# attinier84-motherboard-mk-2_1.net
KiCad netlist of a schematic drawn in EAGLE
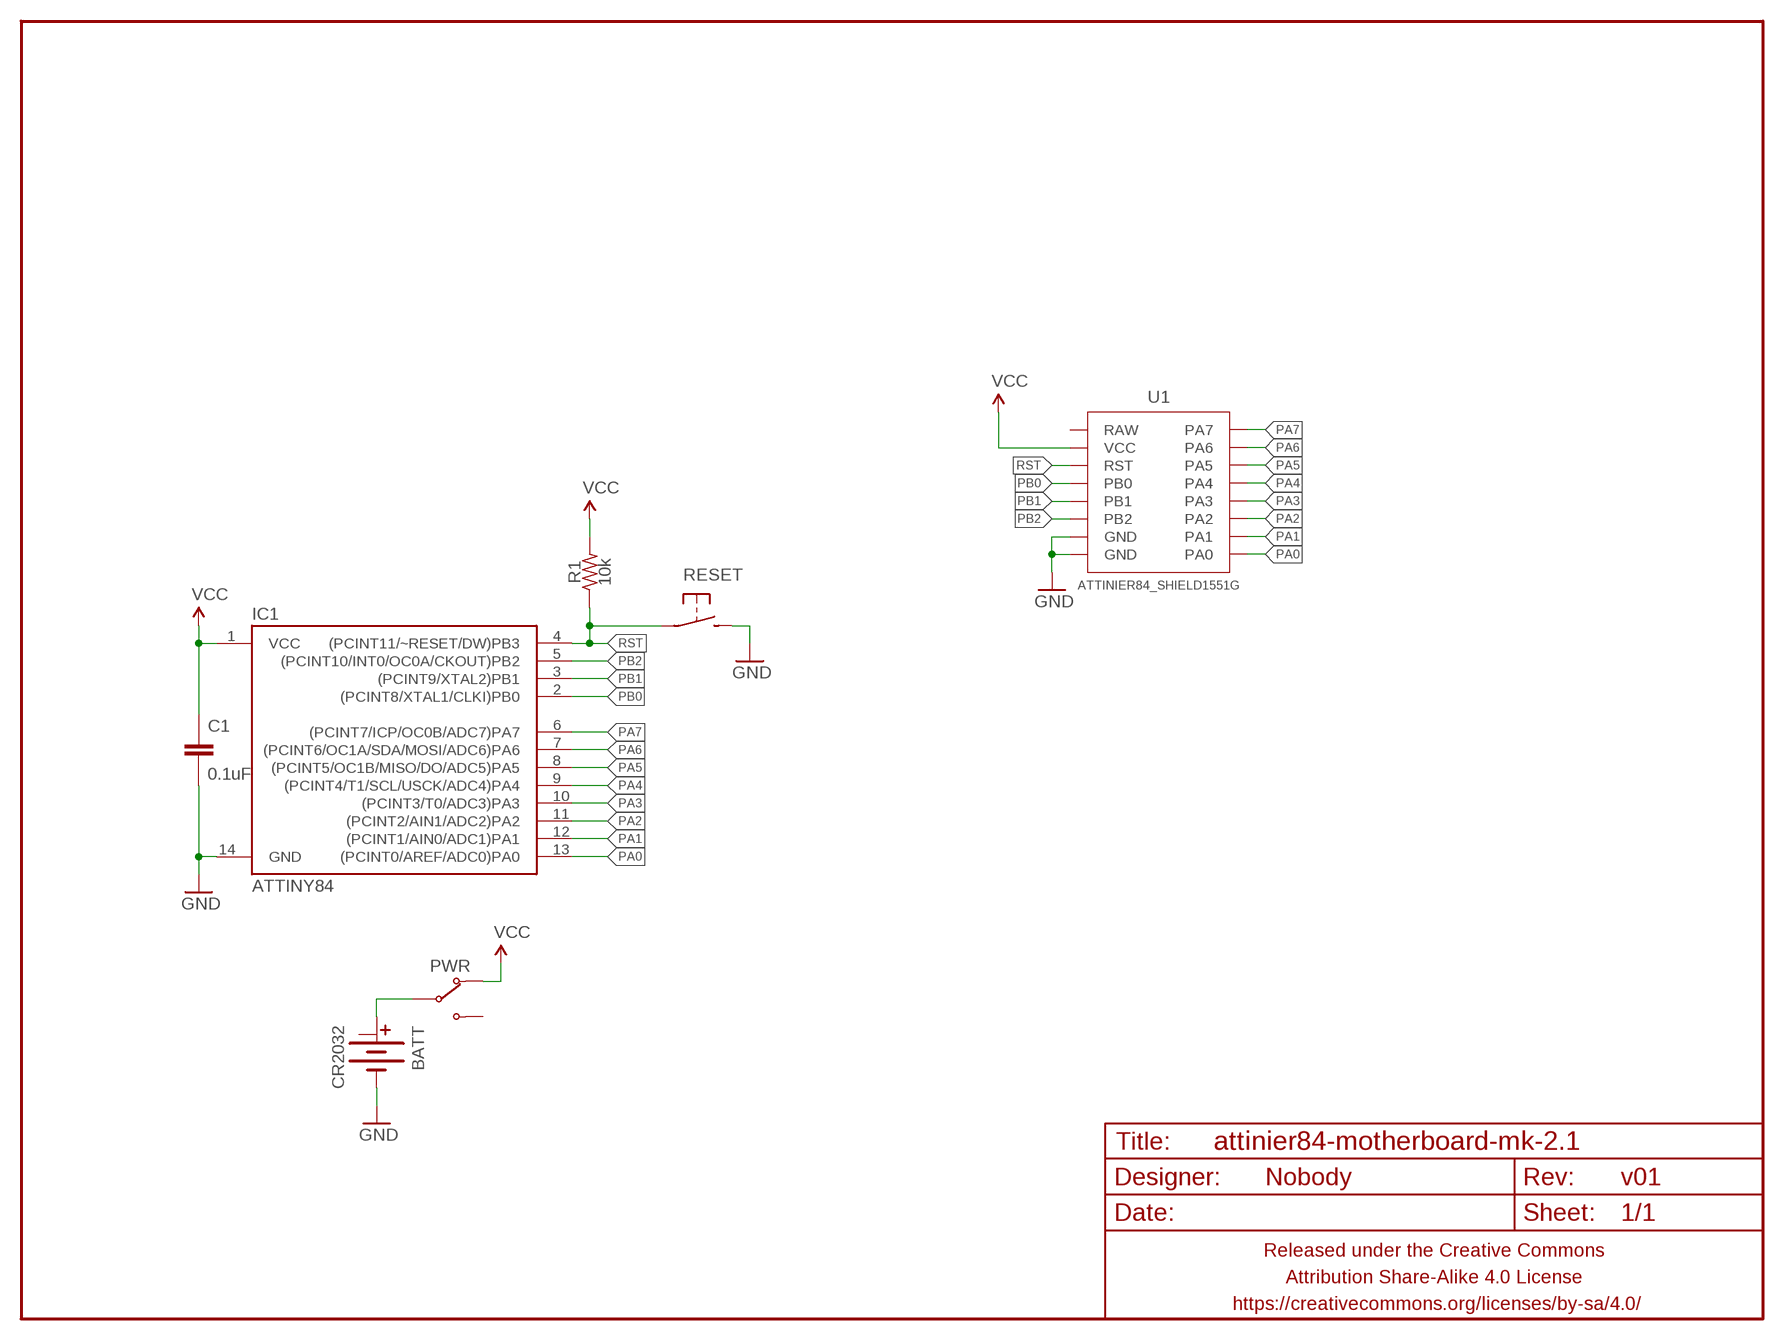
[diagram p0: schematic, sheet 1]

(export (version "E")
  (design (tool "Eeschema 10.0.6"))
  (components
    (comp (ref "BATT")
      (value "CR2032")
      (footprint "eagle-import:BATTCON_20MM_MINE")
      (libsource (lib "eagle-import") (part "BATTERY-COINCR2032_SMD"))
    )
    (comp (ref "C1")
      (value "0.1uF")
      (footprint "eagle-import:C0805")
      (libsource (lib "eagle-import") (part "CAPACITOR-CERAMICC0805"))
    )
    (comp (ref "FRAME1")
      (value "FRAME-LETTERNO_PACKAGE")
      (footprint "eagle-import:DUMMY")
      (fields (field (name "DESIGNER") "Nobody"))
      (libsource (lib "eagle-import") (part "FRAME-LETTERNO_PACKAGE"))
    )
    (comp (ref "IC1")
      (value "ATTINY84")
      (footprint "eagle-import:SO14")
      (libsource (lib "eagle-import") (part "ATTINY84"))
    )
    (comp (ref "PWR")
      (value "SWITCH-SPDTPTH-RA-2.54MM")
      (footprint "eagle-import:SPDT-RA-2.54MM")
      (libsource (lib "eagle-import") (part "SWITCH-SPDTPTH-RA-2.54MM"))
    )
    (comp (ref "R1")
      (value "10k")
      (footprint "eagle-import:R0805")
      (libsource (lib "eagle-import") (part "RESISTORR0805"))
    )
    (comp (ref "RESET")
      (value "SPST-NO-TACT3MM-PTH-SMALL-PADS")
      (footprint "eagle-import:DTS-3-SMALL-PADS")
      (libsource (lib "eagle-import") (part "SPST-NO-TACT3MM-PTH-SMALL-PADS"))
    )
    (comp (ref "U1")
      (value "ATTINIER84_SHIELD1551G")
      (footprint "eagle-import:ATTINIER84_SHIELD2")
      (libsource (lib "eagle-import") (part "ATTINIER84_SHIELD1551G"))
    )
  )
  (nets
    (net (code "1") (name "GND") (class "Default")
      (node (ref "BATT") (pin "BOTTOM") (pinfunction "-_BOTTOM") (pintype "bidirectional"))
      (node (ref "C1") (pin "2") (pinfunction "2_2") (pintype "passive"))
      (node (ref "IC1") (pin "14") (pinfunction "GND_14") (pintype "bidirectional"))
      (node (ref "RESET") (pin "2") (pinfunction "2_2") (pintype "passive"))
      (node (ref "U1") (pin "GND@1") (pinfunction "GND_GND@1") (pintype "bidirectional"))
      (node (ref "U1") (pin "GND@2") (pinfunction "GND_GND@2") (pintype "bidirectional"))
    )
    (net (code "2") (name "Net-(BATT-+)") (class "Default")
      (node (ref "BATT") (pin "TOP@1") (pinfunction "+_TOP@1") (pintype "bidirectional"))
      (node (ref "PWR") (pin "2") (pinfunction "COM_2") (pintype "passive"))
    )
    (net (code "3") (name "PA0") (class "Default")
      (node (ref "IC1") (pin "13") (pinfunction "(PCINT0/AREF/ADC0)PA0_13") (pintype "bidirectional"))
      (node (ref "U1") (pin "PA0") (pinfunction "PA0_PA0") (pintype "bidirectional"))
    )
    (net (code "4") (name "PA1") (class "Default")
      (node (ref "IC1") (pin "12") (pinfunction "(PCINT1/AIN0/ADC1)PA1_12") (pintype "bidirectional"))
      (node (ref "U1") (pin "PA1") (pinfunction "PA1_PA1") (pintype "bidirectional"))
    )
    (net (code "5") (name "PA2") (class "Default")
      (node (ref "IC1") (pin "11") (pinfunction "(PCINT2/AIN1/ADC2)PA2_11") (pintype "bidirectional"))
      (node (ref "U1") (pin "PA2") (pinfunction "PA2_PA2") (pintype "bidirectional"))
    )
    (net (code "6") (name "PA3") (class "Default")
      (node (ref "IC1") (pin "10") (pinfunction "(PCINT3/T0/ADC3)PA3_10") (pintype "bidirectional"))
      (node (ref "U1") (pin "PA3") (pinfunction "PA3_PA3") (pintype "bidirectional"))
    )
    (net (code "7") (name "PA4") (class "Default")
      (node (ref "IC1") (pin "9") (pinfunction "(PCINT4/T1/SCL/USCK/ADC4)PA4_9") (pintype "bidirectional"))
      (node (ref "U1") (pin "PA4") (pinfunction "PA4_PA4") (pintype "bidirectional"))
    )
    (net (code "8") (name "PA5") (class "Default")
      (node (ref "IC1") (pin "8") (pinfunction "(PCINT5/OC1B/MISO/DO/ADC5)PA5_8") (pintype "bidirectional"))
      (node (ref "U1") (pin "PA5") (pinfunction "PA5_PA5") (pintype "bidirectional"))
    )
    (net (code "9") (name "PA6") (class "Default")
      (node (ref "IC1") (pin "7") (pinfunction "(PCINT6/OC1A/SDA/MOSI/ADC6)PA6_7") (pintype "bidirectional"))
      (node (ref "U1") (pin "PA6") (pinfunction "PA6_PA6") (pintype "bidirectional"))
    )
    (net (code "10") (name "PA7") (class "Default")
      (node (ref "IC1") (pin "6") (pinfunction "(PCINT7/ICP/OC0B/ADC7)PA7_6") (pintype "bidirectional"))
      (node (ref "U1") (pin "PA7") (pinfunction "PA7_PA7") (pintype "bidirectional"))
    )
    (net (code "11") (name "PB0") (class "Default")
      (node (ref "IC1") (pin "2") (pinfunction "(PCINT8/XTAL1/CLKI)PB0_2") (pintype "bidirectional"))
      (node (ref "U1") (pin "PB0") (pinfunction "PB0_PB0") (pintype "bidirectional"))
    )
    (net (code "12") (name "PB1") (class "Default")
      (node (ref "IC1") (pin "3") (pinfunction "(PCINT9/XTAL2)PB1_3") (pintype "bidirectional"))
      (node (ref "U1") (pin "PB1") (pinfunction "PB1_PB1") (pintype "bidirectional"))
    )
    (net (code "13") (name "PB2") (class "Default")
      (node (ref "IC1") (pin "5") (pinfunction "(PCINT10/INT0/OC0A/CKOUT)PB2_5") (pintype "bidirectional"))
      (node (ref "U1") (pin "PB2") (pinfunction "PB2_PB2") (pintype "bidirectional"))
    )
    (net (code "14") (name "RST") (class "Default")
      (node (ref "IC1") (pin "4") (pinfunction "(PCINT11/~{RESET/DW})PB3_4") (pintype "bidirectional"))
      (node (ref "R1") (pin "1") (pinfunction "1_1") (pintype "passive"))
      (node (ref "RESET") (pin "1") (pinfunction "1_1") (pintype "passive"))
      (node (ref "U1") (pin "RST") (pinfunction "RST_RST") (pintype "bidirectional"))
    )
    (net (code "15") (name "VCC") (class "Default")
      (node (ref "C1") (pin "1") (pinfunction "1_1") (pintype "passive"))
      (node (ref "IC1") (pin "1") (pinfunction "VCC_1") (pintype "bidirectional"))
      (node (ref "PWR") (pin "1") (pinfunction "NC_1") (pintype "passive"))
      (node (ref "R1") (pin "2") (pinfunction "2_2") (pintype "passive"))
      (node (ref "U1") (pin "VCC") (pinfunction "VCC_VCC") (pintype "bidirectional"))
    )
    (net (code "16") (name "unconnected-(BATT-+1-PadTOP@2)") (class "Default")
      (node (ref "BATT") (pin "TOP@2") (pinfunction "+1_TOP@2") (pintype "bidirectional"))
    )
    (net (code "17") (name "unconnected-(PWR-NO-Pad3)") (class "Default")
      (node (ref "PWR") (pin "3") (pinfunction "NO_3") (pintype "passive"))
    )
    (net (code "18") (name "unconnected-(U1-PadRAW)") (class "Default")
      (node (ref "U1") (pin "RAW") (pinfunction "RAW_RAW") (pintype "bidirectional"))
    )
  )
)
